# PGTN005_filter.net
KiCad netlist of a schematic drawn in EAGLE
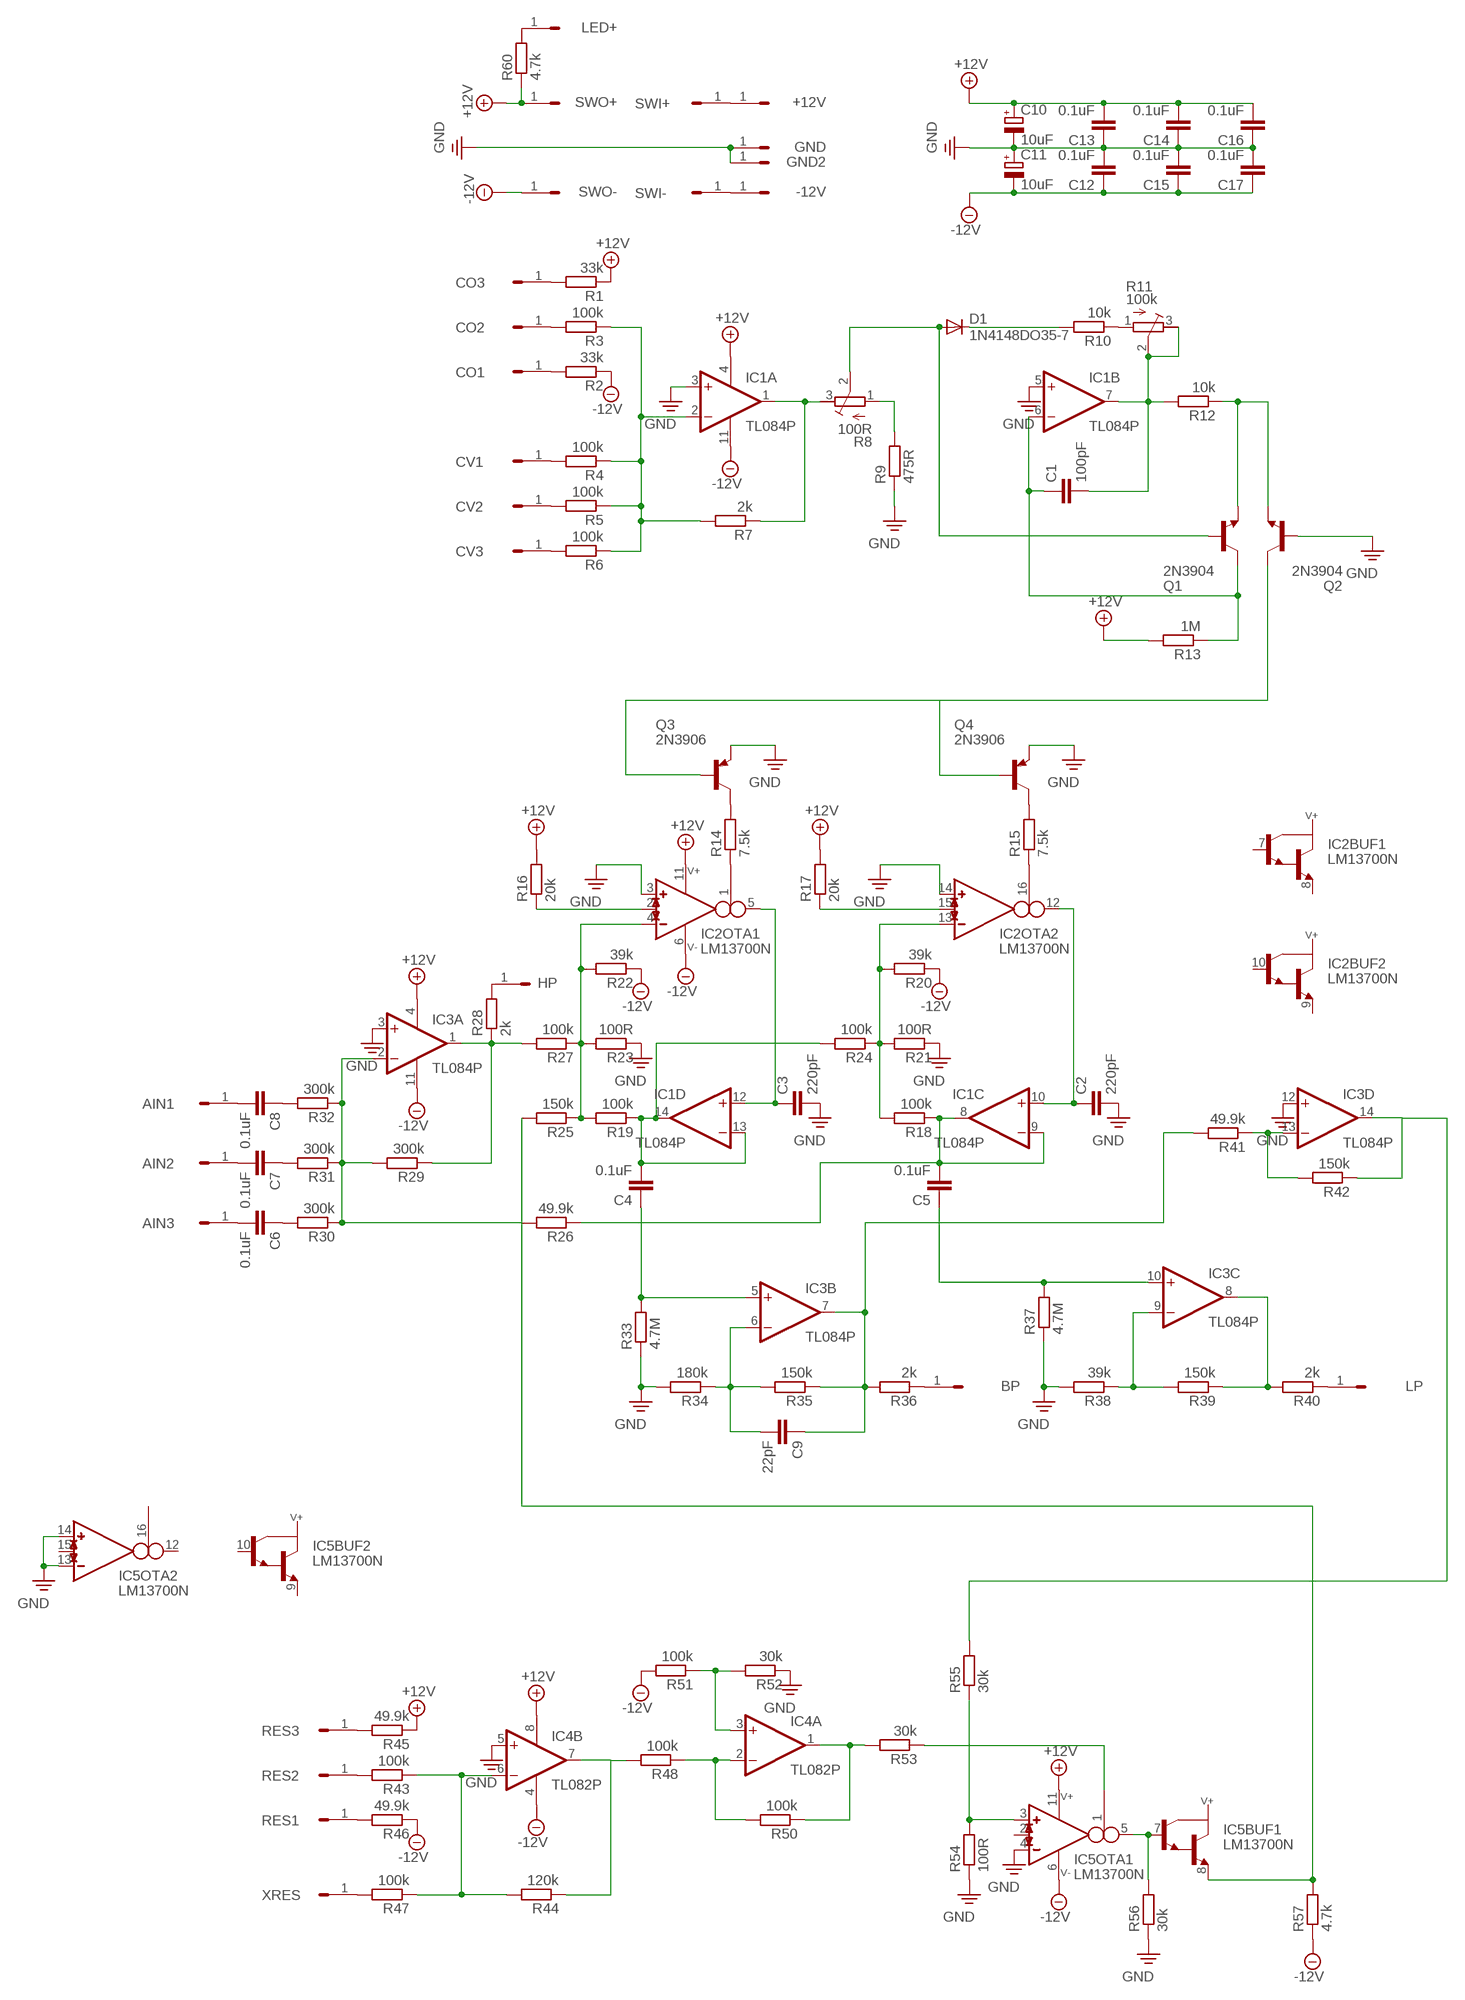
[diagram p0: schematic, sheet 1]

(export (version "E")
  (design (tool "Eeschema 10.0.6"))
  (components
    (comp (ref "+12V")
      (value "HEADER/MALE/01")
      (footprint "eagle-import:HEADER_MALE_01")
      (libsource (lib "eagle-import") (part "HEADER/MALE/01"))
    )
    (comp (ref "-12V")
      (value "HEADER/MALE/01")
      (footprint "eagle-import:HEADER_MALE_01")
      (libsource (lib "eagle-import") (part "HEADER/MALE/01"))
    )
    (comp (ref "AIN1")
      (value "HEADER/MALE/01")
      (footprint "eagle-import:HEADER_MALE_01")
      (libsource (lib "eagle-import") (part "HEADER/MALE/01"))
    )
    (comp (ref "AIN2")
      (value "HEADER/MALE/01")
      (footprint "eagle-import:HEADER_MALE_01")
      (libsource (lib "eagle-import") (part "HEADER/MALE/01"))
    )
    (comp (ref "AIN3")
      (value "HEADER/MALE/01")
      (footprint "eagle-import:HEADER_MALE_01")
      (libsource (lib "eagle-import") (part "HEADER/MALE/01"))
    )
    (comp (ref "BP")
      (value "HEADER/MALE/01")
      (footprint "eagle-import:HEADER_MALE_01")
      (libsource (lib "eagle-import") (part "HEADER/MALE/01"))
    )
    (comp (ref "C1")
      (value "100pF")
      (footprint "eagle-import:CERAMICDISC_5")
      (libsource (lib "eagle-import") (part "CAPACITORCERAMICDISC/5"))
    )
    (comp (ref "C2")
      (value "220pF")
      (footprint "eagle-import:CERAMICDISC_5")
      (libsource (lib "eagle-import") (part "CAPACITORCERAMICDISC/5"))
    )
    (comp (ref "C3")
      (value "220pF")
      (footprint "eagle-import:CERAMICDISC_5")
      (libsource (lib "eagle-import") (part "CAPACITORCERAMICDISC/5"))
    )
    (comp (ref "C4")
      (value "0.1uF")
      (footprint "eagle-import:CERAMICDISC_5")
      (libsource (lib "eagle-import") (part "CAPACITORCERAMICDISC/5"))
    )
    (comp (ref "C5")
      (value "0.1uF")
      (footprint "eagle-import:CERAMICDISC_5")
      (libsource (lib "eagle-import") (part "CAPACITORCERAMICDISC/5"))
    )
    (comp (ref "C6")
      (value "0.1uF")
      (footprint "eagle-import:CERAMICDISC_5")
      (libsource (lib "eagle-import") (part "CAPACITORCERAMICDISC/5"))
    )
    (comp (ref "C7")
      (value "0.1uF")
      (footprint "eagle-import:CERAMICDISC_5")
      (libsource (lib "eagle-import") (part "CAPACITORCERAMICDISC/5"))
    )
    (comp (ref "C8")
      (value "0.1uF")
      (footprint "eagle-import:CERAMICDISC_5")
      (libsource (lib "eagle-import") (part "CAPACITORCERAMICDISC/5"))
    )
    (comp (ref "C9")
      (value "22pF")
      (footprint "eagle-import:CERAMICDISC_5")
      (libsource (lib "eagle-import") (part "CAPACITORCERAMICDISC/5"))
    )
    (comp (ref "C10")
      (value "10uF")
      (footprint "eagle-import:E2,5-6")
      (libsource (lib "eagle-import") (part "CAPACITOR/POLARIZEDE2.5-6"))
    )
    (comp (ref "C11")
      (value "10uF")
      (footprint "eagle-import:E2,5-6")
      (libsource (lib "eagle-import") (part "CAPACITOR/POLARIZEDE2.5-6"))
    )
    (comp (ref "C12")
      (value "0.1uF")
      (footprint "eagle-import:CERAMICDISC_5")
      (libsource (lib "eagle-import") (part "CAPACITORCERAMICDISC/5"))
    )
    (comp (ref "C13")
      (value "0.1uF")
      (footprint "eagle-import:CERAMICDISC_5")
      (libsource (lib "eagle-import") (part "CAPACITORCERAMICDISC/5"))
    )
    (comp (ref "C14")
      (value "0.1uF")
      (footprint "eagle-import:CERAMICDISC_5")
      (libsource (lib "eagle-import") (part "CAPACITORCERAMICDISC/5"))
    )
    (comp (ref "C15")
      (value "0.1uF")
      (footprint "eagle-import:CERAMICDISC_5")
      (libsource (lib "eagle-import") (part "CAPACITORCERAMICDISC/5"))
    )
    (comp (ref "C16")
      (value "0.1uF")
      (footprint "eagle-import:CERAMICDISC_5")
      (libsource (lib "eagle-import") (part "CAPACITORCERAMICDISC/5"))
    )
    (comp (ref "C17")
      (value "0.1uF")
      (footprint "eagle-import:CERAMICDISC_5")
      (libsource (lib "eagle-import") (part "CAPACITORCERAMICDISC/5"))
    )
    (comp (ref "CO1")
      (value "HEADER/MALE/01")
      (footprint "eagle-import:HEADER_MALE_01")
      (libsource (lib "eagle-import") (part "HEADER/MALE/01"))
    )
    (comp (ref "CO2")
      (value "HEADER/MALE/01")
      (footprint "eagle-import:HEADER_MALE_01")
      (libsource (lib "eagle-import") (part "HEADER/MALE/01"))
    )
    (comp (ref "CO3")
      (value "HEADER/MALE/01")
      (footprint "eagle-import:HEADER_MALE_01")
      (libsource (lib "eagle-import") (part "HEADER/MALE/01"))
    )
    (comp (ref "CV1")
      (value "HEADER/MALE/01")
      (footprint "eagle-import:HEADER_MALE_01")
      (libsource (lib "eagle-import") (part "HEADER/MALE/01"))
    )
    (comp (ref "CV2")
      (value "HEADER/MALE/01")
      (footprint "eagle-import:HEADER_MALE_01")
      (libsource (lib "eagle-import") (part "HEADER/MALE/01"))
    )
    (comp (ref "CV3")
      (value "HEADER/MALE/01")
      (footprint "eagle-import:HEADER_MALE_01")
      (libsource (lib "eagle-import") (part "HEADER/MALE/01"))
    )
    (comp (ref "D1")
      (value "1N4148DO35-7")
      (footprint "eagle-import:DO35-7")
      (libsource (lib "eagle-import") (part "1N4148DO35-7"))
    )
    (comp (ref "GND")
      (value "HEADER/MALE/01")
      (footprint "eagle-import:HEADER_MALE_01")
      (libsource (lib "eagle-import") (part "HEADER/MALE/01"))
    )
    (comp (ref "GND2")
      (value "HEADER/MALE/01")
      (footprint "eagle-import:HEADER_MALE_01")
      (libsource (lib "eagle-import") (part "HEADER/MALE/01"))
    )
    (comp (ref "HP")
      (value "HEADER/MALE/01")
      (footprint "eagle-import:HEADER_MALE_01")
      (libsource (lib "eagle-import") (part "HEADER/MALE/01"))
    )
    (comp (ref "IC1")
      (value "TL084P")
      (footprint "eagle-import:DIL14")
      (libsource (lib "eagle-import") (part "TL084P"))
    )
    (comp (ref "IC2")
      (value "LM13700N")
      (footprint "eagle-import:DIL16")
      (libsource (lib "eagle-import") (part "LM13700N"))
    )
    (comp (ref "IC3")
      (value "TL084P")
      (footprint "eagle-import:DIL14")
      (libsource (lib "eagle-import") (part "TL084P"))
    )
    (comp (ref "IC4")
      (value "TL082P")
      (footprint "eagle-import:DIL08")
      (libsource (lib "eagle-import") (part "TL082P"))
    )
    (comp (ref "IC5")
      (value "LM13700N")
      (footprint "eagle-import:DIL16")
      (libsource (lib "eagle-import") (part "LM13700N"))
    )
    (comp (ref "LED+")
      (value "HEADER/MALE/01")
      (footprint "eagle-import:HEADER_MALE_01")
      (libsource (lib "eagle-import") (part "HEADER/MALE/01"))
    )
    (comp (ref "LP")
      (value "HEADER/MALE/01")
      (footprint "eagle-import:HEADER_MALE_01")
      (libsource (lib "eagle-import") (part "HEADER/MALE/01"))
    )
    (comp (ref "Q1")
      (value "2N3904")
      (footprint "eagle-import:TO92")
      (libsource (lib "eagle-import") (part "2N3904"))
    )
    (comp (ref "Q2")
      (value "2N3904")
      (footprint "eagle-import:TO92")
      (libsource (lib "eagle-import") (part "2N3904"))
    )
    (comp (ref "Q3")
      (value "2N3906")
      (footprint "eagle-import:TO92")
      (libsource (lib "eagle-import") (part "2N3906"))
    )
    (comp (ref "Q4")
      (value "2N3906")
      (footprint "eagle-import:TO92")
      (libsource (lib "eagle-import") (part "2N3906"))
    )
    (comp (ref "R1")
      (value "33k")
      (footprint "eagle-import:RESISTOR_7.5")
      (libsource (lib "eagle-import") (part "RESISTORRESISTOR/UPRIGHT/7.5"))
    )
    (comp (ref "R2")
      (value "33k")
      (footprint "eagle-import:RESISTOR_7.5")
      (libsource (lib "eagle-import") (part "RESISTORRESISTOR/UPRIGHT/7.5"))
    )
    (comp (ref "R3")
      (value "100k")
      (footprint "eagle-import:RESISTOR_7.5")
      (libsource (lib "eagle-import") (part "RESISTORRESISTOR/UPRIGHT/7.5"))
    )
    (comp (ref "R4")
      (value "100k")
      (footprint "eagle-import:RESISTOR_7.5")
      (libsource (lib "eagle-import") (part "RESISTORRESISTOR/UPRIGHT/7.5"))
    )
    (comp (ref "R5")
      (value "100k")
      (footprint "eagle-import:RESISTOR_7.5")
      (libsource (lib "eagle-import") (part "RESISTORRESISTOR/UPRIGHT/7.5"))
    )
    (comp (ref "R6")
      (value "100k")
      (footprint "eagle-import:RESISTOR_7.5")
      (libsource (lib "eagle-import") (part "RESISTORRESISTOR/UPRIGHT/7.5"))
    )
    (comp (ref "R7")
      (value "2k")
      (footprint "eagle-import:RESISTOR_7.5")
      (libsource (lib "eagle-import") (part "RESISTORRESISTOR/UPRIGHT/7.5"))
    )
    (comp (ref "R8")
      (value "100R")
      (footprint "eagle-import:TRIMMER_64B")
      (libsource (lib "eagle-import") (part "TRIMMER64X"))
    )
    (comp (ref "R9")
      (value "475R")
      (footprint "eagle-import:RESISTOR_7.5")
      (libsource (lib "eagle-import") (part "RESISTORRESISTOR/UPRIGHT/7.5"))
    )
    (comp (ref "R10")
      (value "10k")
      (footprint "eagle-import:RESISTOR_7.5")
      (libsource (lib "eagle-import") (part "RESISTORRESISTOR/UPRIGHT/7.5"))
    )
    (comp (ref "R11")
      (value "100k")
      (footprint "eagle-import:TRIMMER_64B")
      (libsource (lib "eagle-import") (part "TRIMMER64X"))
    )
    (comp (ref "R12")
      (value "10k")
      (footprint "eagle-import:RESISTOR_7.5")
      (libsource (lib "eagle-import") (part "RESISTORRESISTOR/UPRIGHT/7.5"))
    )
    (comp (ref "R13")
      (value "1M")
      (footprint "eagle-import:RESISTOR_7.5")
      (libsource (lib "eagle-import") (part "RESISTORRESISTOR/UPRIGHT/7.5"))
    )
    (comp (ref "R14")
      (value "7.5k")
      (footprint "eagle-import:RESISTOR_7.5")
      (libsource (lib "eagle-import") (part "RESISTORRESISTOR/UPRIGHT/7.5"))
    )
    (comp (ref "R15")
      (value "7.5k")
      (footprint "eagle-import:RESISTOR_7.5")
      (libsource (lib "eagle-import") (part "RESISTORRESISTOR/UPRIGHT/7.5"))
    )
    (comp (ref "R16")
      (value "20k")
      (footprint "eagle-import:RESISTOR_7.5")
      (libsource (lib "eagle-import") (part "RESISTORRESISTOR/UPRIGHT/7.5"))
    )
    (comp (ref "R17")
      (value "20k")
      (footprint "eagle-import:RESISTOR_7.5")
      (libsource (lib "eagle-import") (part "RESISTORRESISTOR/UPRIGHT/7.5"))
    )
    (comp (ref "R18")
      (value "100k")
      (footprint "eagle-import:RESISTOR_7.5")
      (libsource (lib "eagle-import") (part "RESISTORRESISTOR/UPRIGHT/7.5"))
    )
    (comp (ref "R19")
      (value "100k")
      (footprint "eagle-import:RESISTOR_7.5")
      (libsource (lib "eagle-import") (part "RESISTORRESISTOR/UPRIGHT/7.5"))
    )
    (comp (ref "R20")
      (value "39k")
      (footprint "eagle-import:RESISTOR_7.5")
      (libsource (lib "eagle-import") (part "RESISTORRESISTOR/UPRIGHT/7.5"))
    )
    (comp (ref "R21")
      (value "100R")
      (footprint "eagle-import:RESISTOR_7.5")
      (libsource (lib "eagle-import") (part "RESISTORRESISTOR/UPRIGHT/7.5"))
    )
    (comp (ref "R22")
      (value "39k")
      (footprint "eagle-import:RESISTOR_7.5")
      (libsource (lib "eagle-import") (part "RESISTORRESISTOR/UPRIGHT/7.5"))
    )
    (comp (ref "R23")
      (value "100R")
      (footprint "eagle-import:RESISTOR_7.5")
      (libsource (lib "eagle-import") (part "RESISTORRESISTOR/UPRIGHT/7.5"))
    )
    (comp (ref "R24")
      (value "100k")
      (footprint "eagle-import:RESISTOR_7.5")
      (libsource (lib "eagle-import") (part "RESISTORRESISTOR/UPRIGHT/7.5"))
    )
    (comp (ref "R25")
      (value "150k")
      (footprint "eagle-import:RESISTOR_7.5")
      (libsource (lib "eagle-import") (part "RESISTORRESISTOR/UPRIGHT/7.5"))
    )
    (comp (ref "R26")
      (value "49.9k")
      (footprint "eagle-import:RESISTOR_7.5")
      (libsource (lib "eagle-import") (part "RESISTORRESISTOR/UPRIGHT/7.5"))
    )
    (comp (ref "R27")
      (value "100k")
      (footprint "eagle-import:RESISTOR_7.5")
      (libsource (lib "eagle-import") (part "RESISTORRESISTOR/UPRIGHT/7.5"))
    )
    (comp (ref "R28")
      (value "2k")
      (footprint "eagle-import:RESISTOR_7.5")
      (libsource (lib "eagle-import") (part "RESISTORRESISTOR/UPRIGHT/7.5"))
    )
    (comp (ref "R29")
      (value "300k")
      (footprint "eagle-import:RESISTOR_7.5")
      (libsource (lib "eagle-import") (part "RESISTORRESISTOR/UPRIGHT/7.5"))
    )
    (comp (ref "R30")
      (value "300k")
      (footprint "eagle-import:RESISTOR_7.5")
      (libsource (lib "eagle-import") (part "RESISTORRESISTOR/UPRIGHT/7.5"))
    )
    (comp (ref "R31")
      (value "300k")
      (footprint "eagle-import:RESISTOR_7.5")
      (libsource (lib "eagle-import") (part "RESISTORRESISTOR/UPRIGHT/7.5"))
    )
    (comp (ref "R32")
      (value "300k")
      (footprint "eagle-import:RESISTOR_7.5")
      (libsource (lib "eagle-import") (part "RESISTORRESISTOR/UPRIGHT/7.5"))
    )
    (comp (ref "R33")
      (value "4.7M")
      (footprint "eagle-import:RESISTOR_7.5")
      (libsource (lib "eagle-import") (part "RESISTORRESISTOR/UPRIGHT/7.5"))
    )
    (comp (ref "R34")
      (value "180k")
      (footprint "eagle-import:RESISTOR_7.5")
      (libsource (lib "eagle-import") (part "RESISTORRESISTOR/UPRIGHT/7.5"))
    )
    (comp (ref "R35")
      (value "150k")
      (footprint "eagle-import:RESISTOR_7.5")
      (libsource (lib "eagle-import") (part "RESISTORRESISTOR/UPRIGHT/7.5"))
    )
    (comp (ref "R36")
      (value "2k")
      (footprint "eagle-import:RESISTOR_7.5")
      (libsource (lib "eagle-import") (part "RESISTORRESISTOR/UPRIGHT/7.5"))
    )
    (comp (ref "R37")
      (value "4.7M")
      (footprint "eagle-import:RESISTOR_7.5")
      (libsource (lib "eagle-import") (part "RESISTORRESISTOR/UPRIGHT/7.5"))
    )
    (comp (ref "R38")
      (value "39k")
      (footprint "eagle-import:RESISTOR_7.5")
      (libsource (lib "eagle-import") (part "RESISTORRESISTOR/UPRIGHT/7.5"))
    )
    (comp (ref "R39")
      (value "150k")
      (footprint "eagle-import:RESISTOR_7.5")
      (libsource (lib "eagle-import") (part "RESISTORRESISTOR/UPRIGHT/7.5"))
    )
    (comp (ref "R40")
      (value "2k")
      (footprint "eagle-import:RESISTOR_7.5")
      (libsource (lib "eagle-import") (part "RESISTORRESISTOR/UPRIGHT/7.5"))
    )
    (comp (ref "R41")
      (value "49.9k")
      (footprint "eagle-import:RESISTOR_7.5")
      (libsource (lib "eagle-import") (part "RESISTORRESISTOR/UPRIGHT/7.5"))
    )
    (comp (ref "R42")
      (value "150k")
      (footprint "eagle-import:RESISTOR_7.5")
      (libsource (lib "eagle-import") (part "RESISTORRESISTOR/UPRIGHT/7.5"))
    )
    (comp (ref "R43")
      (value "100k")
      (footprint "eagle-import:RESISTOR_7.5")
      (libsource (lib "eagle-import") (part "RESISTORRESISTOR/UPRIGHT/7.5"))
    )
    (comp (ref "R44")
      (value "120k")
      (footprint "eagle-import:RESISTOR_7.5")
      (libsource (lib "eagle-import") (part "RESISTORRESISTOR/UPRIGHT/7.5"))
    )
    (comp (ref "R45")
      (value "49.9k")
      (footprint "eagle-import:RESISTOR_7.5")
      (libsource (lib "eagle-import") (part "RESISTORRESISTOR/UPRIGHT/7.5"))
    )
    (comp (ref "R46")
      (value "49.9k")
      (footprint "eagle-import:RESISTOR_7.5")
      (libsource (lib "eagle-import") (part "RESISTORRESISTOR/UPRIGHT/7.5"))
    )
    (comp (ref "R47")
      (value "100k")
      (footprint "eagle-import:RESISTOR_7.5")
      (libsource (lib "eagle-import") (part "RESISTORRESISTOR/UPRIGHT/7.5"))
    )
    (comp (ref "R48")
      (value "100k")
      (footprint "eagle-import:RESISTOR_7.5")
      (libsource (lib "eagle-import") (part "RESISTORRESISTOR/UPRIGHT/7.5"))
    )
    (comp (ref "R50")
      (value "100k")
      (footprint "eagle-import:RESISTOR_7.5")
      (libsource (lib "eagle-import") (part "RESISTORRESISTOR/UPRIGHT/7.5"))
    )
    (comp (ref "R51")
      (value "100k")
      (footprint "eagle-import:RESISTOR_7.5")
      (libsource (lib "eagle-import") (part "RESISTORRESISTOR/UPRIGHT/7.5"))
    )
    (comp (ref "R52")
      (value "30k")
      (footprint "eagle-import:RESISTOR_7.5")
      (libsource (lib "eagle-import") (part "RESISTORRESISTOR/UPRIGHT/7.5"))
    )
    (comp (ref "R53")
      (value "30k")
      (footprint "eagle-import:RESISTOR_7.5")
      (libsource (lib "eagle-import") (part "RESISTORRESISTOR/UPRIGHT/7.5"))
    )
    (comp (ref "R54")
      (value "100R")
      (footprint "eagle-import:RESISTOR_7.5")
      (libsource (lib "eagle-import") (part "RESISTORRESISTOR/UPRIGHT/7.5"))
    )
    (comp (ref "R55")
      (value "30k")
      (footprint "eagle-import:RESISTOR_7.5")
      (libsource (lib "eagle-import") (part "RESISTORRESISTOR/UPRIGHT/7.5"))
    )
    (comp (ref "R56")
      (value "30k")
      (footprint "eagle-import:RESISTOR_7.5")
      (libsource (lib "eagle-import") (part "RESISTORRESISTOR/UPRIGHT/7.5"))
    )
    (comp (ref "R57")
      (value "4.7k")
      (footprint "eagle-import:RESISTOR_7.5")
      (libsource (lib "eagle-import") (part "RESISTORRESISTOR/UPRIGHT/7.5"))
    )
    (comp (ref "R60")
      (value "4.7k")
      (footprint "eagle-import:RESISTOR_7.5")
      (libsource (lib "eagle-import") (part "RESISTORRESISTOR/UPRIGHT/7.5"))
    )
    (comp (ref "RES1")
      (value "HEADER/MALE/01")
      (footprint "eagle-import:HEADER_MALE_01")
      (libsource (lib "eagle-import") (part "HEADER/MALE/01"))
    )
    (comp (ref "RES2")
      (value "HEADER/MALE/01")
      (footprint "eagle-import:HEADER_MALE_01")
      (libsource (lib "eagle-import") (part "HEADER/MALE/01"))
    )
    (comp (ref "RES3")
      (value "HEADER/MALE/01")
      (footprint "eagle-import:HEADER_MALE_01")
      (libsource (lib "eagle-import") (part "HEADER/MALE/01"))
    )
    (comp (ref "SWI+")
      (value "HEADER/MALE/01")
      (footprint "eagle-import:HEADER_MALE_01")
      (libsource (lib "eagle-import") (part "HEADER/MALE/01"))
    )
    (comp (ref "SWI-")
      (value "HEADER/MALE/01")
      (footprint "eagle-import:HEADER_MALE_01")
      (libsource (lib "eagle-import") (part "HEADER/MALE/01"))
    )
    (comp (ref "SWO+")
      (value "HEADER/MALE/01")
      (footprint "eagle-import:HEADER_MALE_01")
      (libsource (lib "eagle-import") (part "HEADER/MALE/01"))
    )
    (comp (ref "SWO-")
      (value "HEADER/MALE/01")
      (footprint "eagle-import:HEADER_MALE_01")
      (libsource (lib "eagle-import") (part "HEADER/MALE/01"))
    )
    (comp (ref "XRES")
      (value "HEADER/MALE/01")
      (footprint "eagle-import:HEADER_MALE_01")
      (libsource (lib "eagle-import") (part "HEADER/MALE/01"))
    )
  )
  (nets
    (net (code "1") (name "+12V") (class "Default")
      (node (ref "C10") (pin "+") (pinfunction "+_+") (pintype "passive"))
      (node (ref "C13") (pin "2") (pinfunction "2_2") (pintype "passive"))
      (node (ref "C14") (pin "2") (pinfunction "2_2") (pintype "passive"))
      (node (ref "C16") (pin "2") (pinfunction "2_2") (pintype "passive"))
      (node (ref "IC1") (pin "4") (pinfunction "V+_4") (pintype "power_in"))
      (node (ref "IC2") (pin "11") (pinfunction "V+_11") (pintype "power_in"))
      (node (ref "IC3") (pin "4") (pinfunction "V+_4") (pintype "power_in"))
      (node (ref "IC4") (pin "8") (pinfunction "V+_8") (pintype "power_in"))
      (node (ref "IC5") (pin "11") (pinfunction "V+_11") (pintype "power_in"))
      (node (ref "R1") (pin "1") (pinfunction "1_1") (pintype "passive"))
      (node (ref "R13") (pin "2") (pinfunction "2_2") (pintype "passive"))
      (node (ref "R16") (pin "2") (pinfunction "2_2") (pintype "passive"))
      (node (ref "R17") (pin "2") (pinfunction "2_2") (pintype "passive"))
      (node (ref "R45") (pin "1") (pinfunction "1_1") (pintype "passive"))
      (node (ref "R60") (pin "1") (pinfunction "1_1") (pintype "passive"))
      (node (ref "SWO+") (pin "1") (pinfunction "3_1") (pintype "passive"))
    )
    (net (code "2") (name "-12V") (class "Default")
      (node (ref "C11") (pin "-") (pinfunction "-_-") (pintype "passive"))
      (node (ref "C12") (pin "1") (pinfunction "1_1") (pintype "passive"))
      (node (ref "C15") (pin "1") (pinfunction "1_1") (pintype "passive"))
      (node (ref "C17") (pin "1") (pinfunction "1_1") (pintype "passive"))
      (node (ref "IC1") (pin "11") (pinfunction "V-_11") (pintype "power_in"))
      (node (ref "IC2") (pin "6") (pinfunction "V-_6") (pintype "power_in"))
      (node (ref "IC3") (pin "11") (pinfunction "V-_11") (pintype "power_in"))
      (node (ref "IC4") (pin "4") (pinfunction "V-_4") (pintype "power_in"))
      (node (ref "IC5") (pin "6") (pinfunction "V-_6") (pintype "power_in"))
      (node (ref "R2") (pin "1") (pinfunction "1_1") (pintype "passive"))
      (node (ref "R20") (pin "1") (pinfunction "1_1") (pintype "passive"))
      (node (ref "R22") (pin "1") (pinfunction "1_1") (pintype "passive"))
      (node (ref "R46") (pin "1") (pinfunction "1_1") (pintype "passive"))
      (node (ref "R51") (pin "2") (pinfunction "2_2") (pintype "passive"))
      (node (ref "R57") (pin "1") (pinfunction "1_1") (pintype "passive"))
      (node (ref "SWO-") (pin "1") (pinfunction "3_1") (pintype "passive"))
    )
    (net (code "3") (name "GND") (class "Default")
      (node (ref "C10") (pin "-") (pinfunction "-_-") (pintype "passive"))
      (node (ref "C11") (pin "+") (pinfunction "+_+") (pintype "passive"))
      (node (ref "C12") (pin "2") (pinfunction "2_2") (pintype "passive"))
      (node (ref "C13") (pin "1") (pinfunction "1_1") (pintype "passive"))
      (node (ref "C14") (pin "1") (pinfunction "1_1") (pintype "passive"))
      (node (ref "C15") (pin "2") (pinfunction "2_2") (pintype "passive"))
      (node (ref "C16") (pin "1") (pinfunction "1_1") (pintype "passive"))
      (node (ref "C17") (pin "2") (pinfunction "2_2") (pintype "passive"))
      (node (ref "C2") (pin "2") (pinfunction "2_2") (pintype "passive"))
      (node (ref "C3") (pin "2") (pinfunction "2_2") (pintype "passive"))
      (node (ref "GND") (pin "1") (pinfunction "3_1") (pintype "passive"))
      (node (ref "GND2") (pin "1") (pinfunction "3_1") (pintype "passive"))
      (node (ref "IC1") (pin "3") (pinfunction "+IN_3") (pintype "input"))
      (node (ref "IC1") (pin "5") (pinfunction "+IN_5") (pintype "input"))
      (node (ref "IC2") (pin "14") (pinfunction "IN_P_14") (pintype "input"))
      (node (ref "IC2") (pin "3") (pinfunction "IN_P_3") (pintype "input"))
      (node (ref "IC3") (pin "12") (pinfunction "+IN_12") (pintype "input"))
      (node (ref "IC3") (pin "3") (pinfunction "+IN_3") (pintype "input"))
      (node (ref "IC4") (pin "5") (pinfunction "+IN_5") (pintype "input"))
      (node (ref "IC5") (pin "13") (pinfunction "IN_N_13") (pintype "input"))
      (node (ref "IC5") (pin "14") (pinfunction "IN_P_14") (pintype "input"))
      (node (ref "IC5") (pin "4") (pinfunction "IN_N_4") (pintype "input"))
      (node (ref "Q2") (pin "2") (pinfunction "B_2") (pintype "passive"))
      (node (ref "Q3") (pin "3") (pinfunction "E_3") (pintype "passive"))
      (node (ref "Q4") (pin "3") (pinfunction "E_3") (pintype "passive"))
      (node (ref "R21") (pin "1") (pinfunction "1_1") (pintype "passive"))
      (node (ref "R23") (pin "1") (pinfunction "1_1") (pintype "passive"))
      (node (ref "R33") (pin "1") (pinfunction "1_1") (pintype "passive"))
      (node (ref "R34") (pin "2") (pinfunction "2_2") (pintype "passive"))
      (node (ref "R37") (pin "1") (pinfunction "1_1") (pintype "passive"))
      (node (ref "R38") (pin "2") (pinfunction "2_2") (pintype "passive"))
      (node (ref "R52") (pin "1") (pinfunction "1_1") (pintype "passive"))
      (node (ref "R54") (pin "1") (pinfunction "1_1") (pintype "passive"))
      (node (ref "R56") (pin "1") (pinfunction "1_1") (pintype "passive"))
      (node (ref "R9") (pin "1") (pinfunction "1_1") (pintype "passive"))
    )
    (net (code "4") (name "Net-(+12V-3)") (class "Default")
      (node (ref "+12V") (pin "1") (pinfunction "3_1") (pintype "passive"))
      (node (ref "SWI+") (pin "1") (pinfunction "3_1") (pintype "passive"))
    )
    (net (code "5") (name "Net-(-12V-3)") (class "Default")
      (node (ref "-12V") (pin "1") (pinfunction "3_1") (pintype "passive"))
      (node (ref "SWI-") (pin "1") (pinfunction "3_1") (pintype "passive"))
    )
    (net (code "6") (name "Net-(AIN1-3)") (class "Default")
      (node (ref "AIN1") (pin "1") (pinfunction "3_1") (pintype "passive"))
      (node (ref "C8") (pin "2") (pinfunction "2_2") (pintype "passive"))
    )
    (net (code "7") (name "Net-(AIN2-3)") (class "Default")
      (node (ref "AIN2") (pin "1") (pinfunction "3_1") (pintype "passive"))
      (node (ref "C7") (pin "2") (pinfunction "2_2") (pintype "passive"))
    )
    (net (code "8") (name "Net-(AIN3-3)") (class "Default")
      (node (ref "AIN3") (pin "1") (pinfunction "3_1") (pintype "passive"))
      (node (ref "C6") (pin "2") (pinfunction "2_2") (pintype "passive"))
    )
    (net (code "9") (name "Net-(BP-3)") (class "Default")
      (node (ref "BP") (pin "1") (pinfunction "3_1") (pintype "passive"))
      (node (ref "R36") (pin "1") (pinfunction "1_1") (pintype "passive"))
    )
    (net (code "10") (name "Net-(C6-Pad1)") (class "Default")
      (node (ref "C6") (pin "1") (pinfunction "1_1") (pintype "passive"))
      (node (ref "R30") (pin "2") (pinfunction "2_2") (pintype "passive"))
    )
    (net (code "11") (name "Net-(C7-Pad1)") (class "Default")
      (node (ref "C7") (pin "1") (pinfunction "1_1") (pintype "passive"))
      (node (ref "R31") (pin "2") (pinfunction "2_2") (pintype "passive"))
    )
    (net (code "12") (name "Net-(C8-Pad1)") (class "Default")
      (node (ref "C8") (pin "1") (pinfunction "1_1") (pintype "passive"))
      (node (ref "R32") (pin "2") (pinfunction "2_2") (pintype "passive"))
    )
    (net (code "13") (name "Net-(CO1-3)") (class "Default")
      (node (ref "CO1") (pin "1") (pinfunction "3_1") (pintype "passive"))
      (node (ref "R2") (pin "2") (pinfunction "2_2") (pintype "passive"))
    )
    (net (code "14") (name "Net-(CO2-3)") (class "Default")
      (node (ref "CO2") (pin "1") (pinfunction "3_1") (pintype "passive"))
      (node (ref "R3") (pin "2") (pinfunction "2_2") (pintype "passive"))
    )
    (net (code "15") (name "Net-(CO3-3)") (class "Default")
      (node (ref "CO3") (pin "1") (pinfunction "3_1") (pintype "passive"))
      (node (ref "R1") (pin "2") (pinfunction "2_2") (pintype "passive"))
    )
    (net (code "16") (name "Net-(CV1-3)") (class "Default")
      (node (ref "CV1") (pin "1") (pinfunction "3_1") (pintype "passive"))
      (node (ref "R4") (pin "2") (pinfunction "2_2") (pintype "passive"))
    )
    (net (code "17") (name "Net-(CV2-3)") (class "Default")
      (node (ref "CV2") (pin "1") (pinfunction "3_1") (pintype "passive"))
      (node (ref "R5") (pin "2") (pinfunction "2_2") (pintype "passive"))
    )
    (net (code "18") (name "Net-(CV3-3)") (class "Default")
      (node (ref "CV3") (pin "1") (pinfunction "3_1") (pintype "passive"))
      (node (ref "R6") (pin "2") (pinfunction "2_2") (pintype "passive"))
    )
    (net (code "19") (name "Net-(D1-PadC)") (class "Default")
      (node (ref "D1") (pin "C") (pinfunction "C_C") (pintype "passive"))
      (node (ref "R10") (pin "2") (pinfunction "2_2") (pintype "passive"))
    )
    (net (code "20") (name "Net-(HP-3)") (class "Default")
      (node (ref "HP") (pin "1") (pinfunction "3_1") (pintype "passive"))
      (node (ref "R28") (pin "2") (pinfunction "2_2") (pintype "passive"))
    )
    (net (code "21") (name "Net-(IC1A--IN)") (class "Default")
      (node (ref "IC1") (pin "2") (pinfunction "-IN_2") (pintype "input"))
      (node (ref "R3") (pin "1") (pinfunction "1_1") (pintype "passive"))
      (node (ref "R4") (pin "1") (pinfunction "1_1") (pintype "passive"))
      (node (ref "R5") (pin "1") (pinfunction "1_1") (pintype "passive"))
      (node (ref "R6") (pin "1") (pinfunction "1_1") (pintype "passive"))
      (node (ref "R7") (pin "2") (pinfunction "2_2") (pintype "passive"))
    )
    (net (code "22") (name "Net-(IC1A-OUT)") (class "Default")
      (node (ref "IC1") (pin "1") (pinfunction "OUT_1") (pintype "output"))
      (node (ref "R7") (pin "1") (pinfunction "1_1") (pintype "passive"))
      (node (ref "R8") (pin "3") (pinfunction "A_3") (pintype "passive"))
    )
    (net (code "23") (name "Net-(IC1B--IN)") (class "Default")
      (node (ref "C1") (pin "1") (pinfunction "1_1") (pintype "passive"))
      (node (ref "IC1") (pin "6") (pinfunction "-IN_6") (pintype "input"))
      (node (ref "Q1") (pin "1") (pinfunction "C_1") (pintype "passive"))
      (node (ref "R13") (pin "1") (pinfunction "1_1") (pintype "passive"))
    )
    (net (code "24") (name "Net-(IC1B-OUT)") (class "Default")
      (node (ref "C1") (pin "2") (pinfunction "2_2") (pintype "passive"))
      (node (ref "IC1") (pin "7") (pinfunction "OUT_7") (pintype "output"))
      (node (ref "R11") (pin "2") (pinfunction "S_2") (pintype "passive"))
      (node (ref "R11") (pin "3") (pinfunction "A_3") (pintype "passive"))
      (node (ref "R12") (pin "2") (pinfunction "2_2") (pintype "passive"))
    )
    (net (code "25") (name "Net-(IC1C-+IN)") (class "Default")
      (node (ref "C2") (pin "1") (pinfunction "1_1") (pintype "passive"))
      (node (ref "IC1") (pin "10") (pinfunction "+IN_10") (pintype "input"))
      (node (ref "IC2") (pin "12") (pinfunction "OUT_12") (pintype "output"))
    )
    (net (code "26") (name "Net-(IC1C--IN)") (class "Default")
      (node (ref "C5") (pin "2") (pinfunction "2_2") (pintype "passive"))
      (node (ref "IC1") (pin "8") (pinfunction "OUT_8") (pintype "output"))
      (node (ref "IC1") (pin "9") (pinfunction "-IN_9") (pintype "input"))
      (node (ref "R18") (pin "1") (pinfunction "1_1") (pintype "passive"))
      (node (ref "R26") (pin "1") (pinfunction "1_1") (pintype "passive"))
    )
    (net (code "27") (name "Net-(IC1D-+IN)") (class "Default")
      (node (ref "C3") (pin "1") (pinfunction "1_1") (pintype "passive"))
      (node (ref "IC1") (pin "12") (pinfunction "+IN_12") (pintype "input"))
      (node (ref "IC2") (pin "5") (pinfunction "OUT_5") (pintype "output"))
    )
    (net (code "28") (name "Net-(IC1D--IN)") (class "Default")
      (node (ref "C4") (pin "2") (pinfunction "2_2") (pintype "passive"))
      (node (ref "IC1") (pin "13") (pinfunction "-IN_13") (pintype "input"))
      (node (ref "IC1") (pin "14") (pinfunction "OUT_14") (pintype "output"))
      (node (ref "R19") (pin "1") (pinfunction "1_1") (pintype "passive"))
      (node (ref "R24") (pin "2") (pinfunction "2_2") (pintype "passive"))
    )
    (net (code "29") (name "Net-(IC2C-IN_N)") (class "Default")
      (node (ref "IC2") (pin "4") (pinfunction "IN_N_4") (pintype "input"))
      (node (ref "R19") (pin "2") (pinfunction "2_2") (pintype "passive"))
      (node (ref "R22") (pin "2") (pinfunction "2_2") (pintype "passive"))
      (node (ref "R23") (pin "2") (pinfunction "2_2") (pintype "passive"))
      (node (ref "R25") (pin "1") (pinfunction "1_1") (pintype "passive"))
      (node (ref "R27") (pin "1") (pinfunction "1_1") (pintype "passive"))
    )
    (net (code "30") (name "Net-(IC2C-I_BIAS)") (class "Default")
      (node (ref "IC2") (pin "1") (pinfunction "I_BIAS_1") (pintype "input"))
      (node (ref "R14") (pin "1") (pinfunction "1_1") (pintype "passive"))
    )
    (net (code "31") (name "Net-(IC2C-I_DIODE)") (class "Default")
      (node (ref "IC2") (pin "2") (pinfunction "I_DIODE_2") (pintype "input"))
      (node (ref "R16") (pin "1") (pinfunction "1_1") (pintype "passive"))
    )
    (net (code "32") (name "Net-(IC2D-IN_N)") (class "Default")
      (node (ref "IC2") (pin "13") (pinfunction "IN_N_13") (pintype "input"))
      (node (ref "R18") (pin "2") (pinfunction "2_2") (pintype "passive"))
      (node (ref "R20") (pin "2") (pinfunction "2_2") (pintype "passive"))
      (node (ref "R21") (pin "2") (pinfunction "2_2") (pintype "passive"))
      (node (ref "R24") (pin "1") (pinfunction "1_1") (pintype "passive"))
    )
    (net (code "33") (name "Net-(IC2D-I_BIAS)") (class "Default")
      (node (ref "IC2") (pin "16") (pinfunction "I_BIAS_16") (pintype "input"))
      (node (ref "R15") (pin "1") (pinfunction "1_1") (pintype "passive"))
    )
    (net (code "34") (name "Net-(IC2D-I_DIODE)") (class "Default")
      (node (ref "IC2") (pin "15") (pinfunction "I_DIODE_15") (pintype "input"))
      (node (ref "R17") (pin "1") (pinfunction "1_1") (pintype "passive"))
    )
    (net (code "35") (name "Net-(IC3A--IN)") (class "Default")
      (node (ref "IC3") (pin "2") (pinfunction "-IN_2") (pintype "input"))
      (node (ref "R26") (pin "2") (pinfunction "2_2") (pintype "passive"))
      (node (ref "R29") (pin "2") (pinfunction "2_2") (pintype "passive"))
      (node (ref "R30") (pin "1") (pinfunction "1_1") (pintype "passive"))
      (node (ref "R31") (pin "1") (pinfunction "1_1") (pintype "passive"))
      (node (ref "R32") (pin "1") (pinfunction "1_1") (pintype "passive"))
    )
    (net (code "36") (name "Net-(IC3A-OUT)") (class "Default")
      (node (ref "IC3") (pin "1") (pinfunction "OUT_1") (pintype "output"))
      (node (ref "R27") (pin "2") (pinfunction "2_2") (pintype "passive"))
      (node (ref "R28") (pin "1") (pinfunction "1_1") (pintype "passive"))
      (node (ref "R29") (pin "1") (pinfunction "1_1") (pintype "passive"))
    )
    (net (code "37") (name "Net-(IC3B-+IN)") (class "Default")
      (node (ref "C4") (pin "1") (pinfunction "1_1") (pintype "passive"))
      (node (ref "IC3") (pin "5") (pinfunction "+IN_5") (pintype "input"))
      (node (ref "R33") (pin "2") (pinfunction "2_2") (pintype "passive"))
    )
    (net (code "38") (name "Net-(IC3B--IN)") (class "Default")
      (node (ref "C9") (pin "2") (pinfunction "2_2") (pintype "passive"))
      (node (ref "IC3") (pin "6") (pinfunction "-IN_6") (pintype "input"))
      (node (ref "R34") (pin "1") (pinfunction "1_1") (pintype "passive"))
      (node (ref "R35") (pin "2") (pinfunction "2_2") (pintype "passive"))
    )
    (net (code "39") (name "Net-(IC3B-OUT)") (class "Default")
      (node (ref "C9") (pin "1") (pinfunction "1_1") (pintype "passive"))
      (node (ref "IC3") (pin "7") (pinfunction "OUT_7") (pintype "output"))
      (node (ref "R35") (pin "1") (pinfunction "1_1") (pintype "passive"))
      (node (ref "R36") (pin "2") (pinfunction "2_2") (pintype "passive"))
      (node (ref "R41") (pin "2") (pinfunction "2_2") (pintype "passive"))
    )
    (net (code "40") (name "Net-(IC3C-+IN)") (class "Default")
      (node (ref "C5") (pin "1") (pinfunction "1_1") (pintype "passive"))
      (node (ref "IC3") (pin "10") (pinfunction "+IN_10") (pintype "input"))
      (node (ref "R37") (pin "2") (pinfunction "2_2") (pintype "passive"))
    )
    (net (code "41") (name "Net-(IC3C--IN)") (class "Default")
      (node (ref "IC3") (pin "9") (pinfunction "-IN_9") (pintype "input"))
      (node (ref "R38") (pin "1") (pinfunction "1_1") (pintype "passive"))
      (node (ref "R39") (pin "2") (pinfunction "2_2") (pintype "passive"))
    )
    (net (code "42") (name "Net-(IC3C-OUT)") (class "Default")
      (node (ref "IC3") (pin "8") (pinfunction "OUT_8") (pintype "output"))
      (node (ref "R39") (pin "1") (pinfunction "1_1") (pintype "passive"))
      (node (ref "R40") (pin "2") (pinfunction "2_2") (pintype "passive"))
    )
    (net (code "43") (name "Net-(IC3D--IN)") (class "Default")
      (node (ref "IC3") (pin "13") (pinfunction "-IN_13") (pintype "input"))
      (node (ref "R41") (pin "1") (pinfunction "1_1") (pintype "passive"))
      (node (ref "R42") (pin "2") (pinfunction "2_2") (pintype "passive"))
    )
    (net (code "44") (name "Net-(IC3D-OUT)") (class "Default")
      (node (ref "IC3") (pin "14") (pinfunction "OUT_14") (pintype "output"))
      (node (ref "R42") (pin "1") (pinfunction "1_1") (pintype "passive"))
      (node (ref "R55") (pin "2") (pinfunction "2_2") (pintype "passive"))
    )
    (net (code "45") (name "Net-(IC4A-+IN)") (class "Default")
      (node (ref "IC4") (pin "3") (pinfunction "+IN_3") (pintype "input"))
      (node (ref "R51") (pin "1") (pinfunction "1_1") (pintype "passive"))
      (node (ref "R52") (pin "2") (pinfunction "2_2") (pintype "passive"))
    )
    (net (code "46") (name "Net-(IC4A--IN)") (class "Default")
      (node (ref "IC4") (pin "2") (pinfunction "-IN_2") (pintype "input"))
      (node (ref "R48") (pin "1") (pinfunction "1_1") (pintype "passive"))
      (node (ref "R50") (pin "2") (pinfunction "2_2") (pintype "passive"))
    )
    (net (code "47") (name "Net-(IC4A-OUT)") (class "Default")
      (node (ref "IC4") (pin "1") (pinfunction "OUT_1") (pintype "output"))
      (node (ref "R50") (pin "1") (pinfunction "1_1") (pintype "passive"))
      (node (ref "R53") (pin "2") (pinfunction "2_2") (pintype "passive"))
    )
    (net (code "48") (name "Net-(IC4B--IN)") (class "Default")
      (node (ref "IC4") (pin "6") (pinfunction "-IN_6") (pintype "input"))
      (node (ref "R43") (pin "1") (pinfunction "1_1") (pintype "passive"))
      (node (ref "R44") (pin "2") (pinfunction "2_2") (pintype "passive"))
      (node (ref "R47") (pin "1") (pinfunction "1_1") (pintype "passive"))
    )
    (net (code "49") (name "Net-(IC4B-OUT)") (class "Default")
      (node (ref "IC4") (pin "7") (pinfunction "OUT_7") (pintype "output"))
      (node (ref "R44") (pin "1") (pinfunction "1_1") (pintype "passive"))
      (node (ref "R48") (pin "2") (pinfunction "2_2") (pintype "passive"))
    )
    (net (code "50") (name "Net-(IC5A-B)") (class "Default")
      (node (ref "IC5") (pin "5") (pinfunction "OUT_5") (pintype "output"))
      (node (ref "IC5") (pin "7") (pinfunction "B_7") (pintype "passive"))
      (node (ref "R56") (pin "2") (pinfunction "2_2") (pintype "passive"))
    )
    (net (code "51") (name "Net-(IC5A-E)") (class "Default")
      (node (ref "IC5") (pin "8") (pinfunction "E_8") (pintype "passive"))
      (node (ref "R25") (pin "2") (pinfunction "2_2") (pintype "passive"))
      (node (ref "R57") (pin "2") (pinfunction "2_2") (pintype "passive"))
    )
    (net (code "52") (name "Net-(IC5C-IN_P)") (class "Default")
      (node (ref "IC5") (pin "3") (pinfunction "IN_P_3") (pintype "input"))
      (node (ref "R54") (pin "2") (pinfunction "2_2") (pintype "passive"))
      (node (ref "R55") (pin "1") (pinfunction "1_1") (pintype "passive"))
    )
    (net (code "53") (name "Net-(IC5C-I_BIAS)") (class "Default")
      (node (ref "IC5") (pin "1") (pinfunction "I_BIAS_1") (pintype "input"))
      (node (ref "R53") (pin "1") (pinfunction "1_1") (pintype "passive"))
    )
    (net (code "54") (name "Net-(LED+-3)") (class "Default")
      (node (ref "LED+") (pin "1") (pinfunction "3_1") (pintype "passive"))
      (node (ref "R60") (pin "2") (pinfunction "2_2") (pintype "passive"))
    )
    (net (code "55") (name "Net-(LP-3)") (class "Default")
      (node (ref "LP") (pin "1") (pinfunction "3_1") (pintype "passive"))
      (node (ref "R40") (pin "1") (pinfunction "1_1") (pintype "passive"))
    )
    (net (code "56") (name "Net-(Q1-B)") (class "Default")
      (node (ref "D1") (pin "A") (pinfunction "A_A") (pintype "passive"))
      (node (ref "Q1") (pin "2") (pinfunction "B_2") (pintype "passive"))
      (node (ref "R8") (pin "2") (pinfunction "S_2") (pintype "passive"))
    )
    (net (code "57") (name "Net-(Q1-E)") (class "Default")
      (node (ref "Q1") (pin "3") (pinfunction "E_3") (pintype "passive"))
      (node (ref "Q2") (pin "3") (pinfunction "E_3") (pintype "passive"))
      (node (ref "R12") (pin "1") (pinfunction "1_1") (pintype "passive"))
    )
    (net (code "58") (name "Net-(Q2-C)") (class "Default")
      (node (ref "Q2") (pin "1") (pinfunction "C_1") (pintype "passive"))
      (node (ref "Q3") (pin "2") (pinfunction "B_2") (pintype "passive"))
      (node (ref "Q4") (pin "2") (pinfunction "B_2") (pintype "passive"))
    )
    (net (code "59") (name "Net-(Q3-C)") (class "Default")
      (node (ref "Q3") (pin "1") (pinfunction "C_1") (pintype "passive"))
      (node (ref "R14") (pin "2") (pinfunction "2_2") (pintype "passive"))
    )
    (net (code "60") (name "Net-(Q4-C)") (class "Default")
      (node (ref "Q4") (pin "1") (pinfunction "C_1") (pintype "passive"))
      (node (ref "R15") (pin "2") (pinfunction "2_2") (pintype "passive"))
    )
    (net (code "61") (name "Net-(R8-E)") (class "Default")
      (node (ref "R8") (pin "1") (pinfunction "E_1") (pintype "passive"))
      (node (ref "R9") (pin "2") (pinfunction "2_2") (pintype "passive"))
    )
    (net (code "62") (name "Net-(R11-E)") (class "Default")
      (node (ref "R10") (pin "1") (pinfunction "1_1") (pintype "passive"))
      (node (ref "R11") (pin "1") (pinfunction "E_1") (pintype "passive"))
    )
    (net (code "63") (name "Net-(RES1-3)") (class "Default")
      (node (ref "R46") (pin "2") (pinfunction "2_2") (pintype "passive"))
      (node (ref "RES1") (pin "1") (pinfunction "3_1") (pintype "passive"))
    )
    (net (code "64") (name "Net-(RES2-3)") (class "Default")
      (node (ref "R43") (pin "2") (pinfunction "2_2") (pintype "passive"))
      (node (ref "RES2") (pin "1") (pinfunction "3_1") (pintype "passive"))
    )
    (net (code "65") (name "Net-(RES3-3)") (class "Default")
      (node (ref "R45") (pin "2") (pinfunction "2_2") (pintype "passive"))
      (node (ref "RES3") (pin "1") (pinfunction "3_1") (pintype "passive"))
    )
    (net (code "66") (name "Net-(XRES-3)") (class "Default")
      (node (ref "R47") (pin "2") (pinfunction "2_2") (pintype "passive"))
      (node (ref "XRES") (pin "1") (pinfunction "3_1") (pintype "passive"))
    )
    (net (code "67") (name "unconnected-(IC2A-B-Pad7)") (class "Default")
      (node (ref "IC2") (pin "7") (pinfunction "B_7") (pintype "passive"))
    )
    (net (code "68") (name "unconnected-(IC2A-E-Pad8)") (class "Default")
      (node (ref "IC2") (pin "8") (pinfunction "E_8") (pintype "passive"))
    )
    (net (code "69") (name "unconnected-(IC2B-B-Pad10)") (class "Default")
      (node (ref "IC2") (pin "10") (pinfunction "B_10") (pintype "passive"))
    )
    (net (code "70") (name "unconnected-(IC2B-E-Pad9)") (class "Default")
      (node (ref "IC2") (pin "9") (pinfunction "E_9") (pintype "passive"))
    )
    (net (code "71") (name "unconnected-(IC5B-B-Pad10)") (class "Default")
      (node (ref "IC5") (pin "10") (pinfunction "B_10") (pintype "passive"))
    )
    (net (code "72") (name "unconnected-(IC5B-E-Pad9)") (class "Default")
      (node (ref "IC5") (pin "9") (pinfunction "E_9") (pintype "passive"))
    )
    (net (code "73") (name "unconnected-(IC5C-I_DIODE-Pad2)") (class "Default")
      (node (ref "IC5") (pin "2") (pinfunction "I_DIODE_2") (pintype "input"))
    )
    (net (code "74") (name "unconnected-(IC5D-I_BIAS-Pad16)") (class "Default")
      (node (ref "IC5") (pin "16") (pinfunction "I_BIAS_16") (pintype "input"))
    )
    (net (code "75") (name "unconnected-(IC5D-I_DIODE-Pad15)") (class "Default")
      (node (ref "IC5") (pin "15") (pinfunction "I_DIODE_15") (pintype "input"))
    )
    (net (code "76") (name "unconnected-(IC5D-OUT-Pad12)") (class "Default")
      (node (ref "IC5") (pin "12") (pinfunction "OUT_12") (pintype "output"))
    )
  )
)
